# tracy.net
KiCad netlist of a schematic drawn in EAGLE
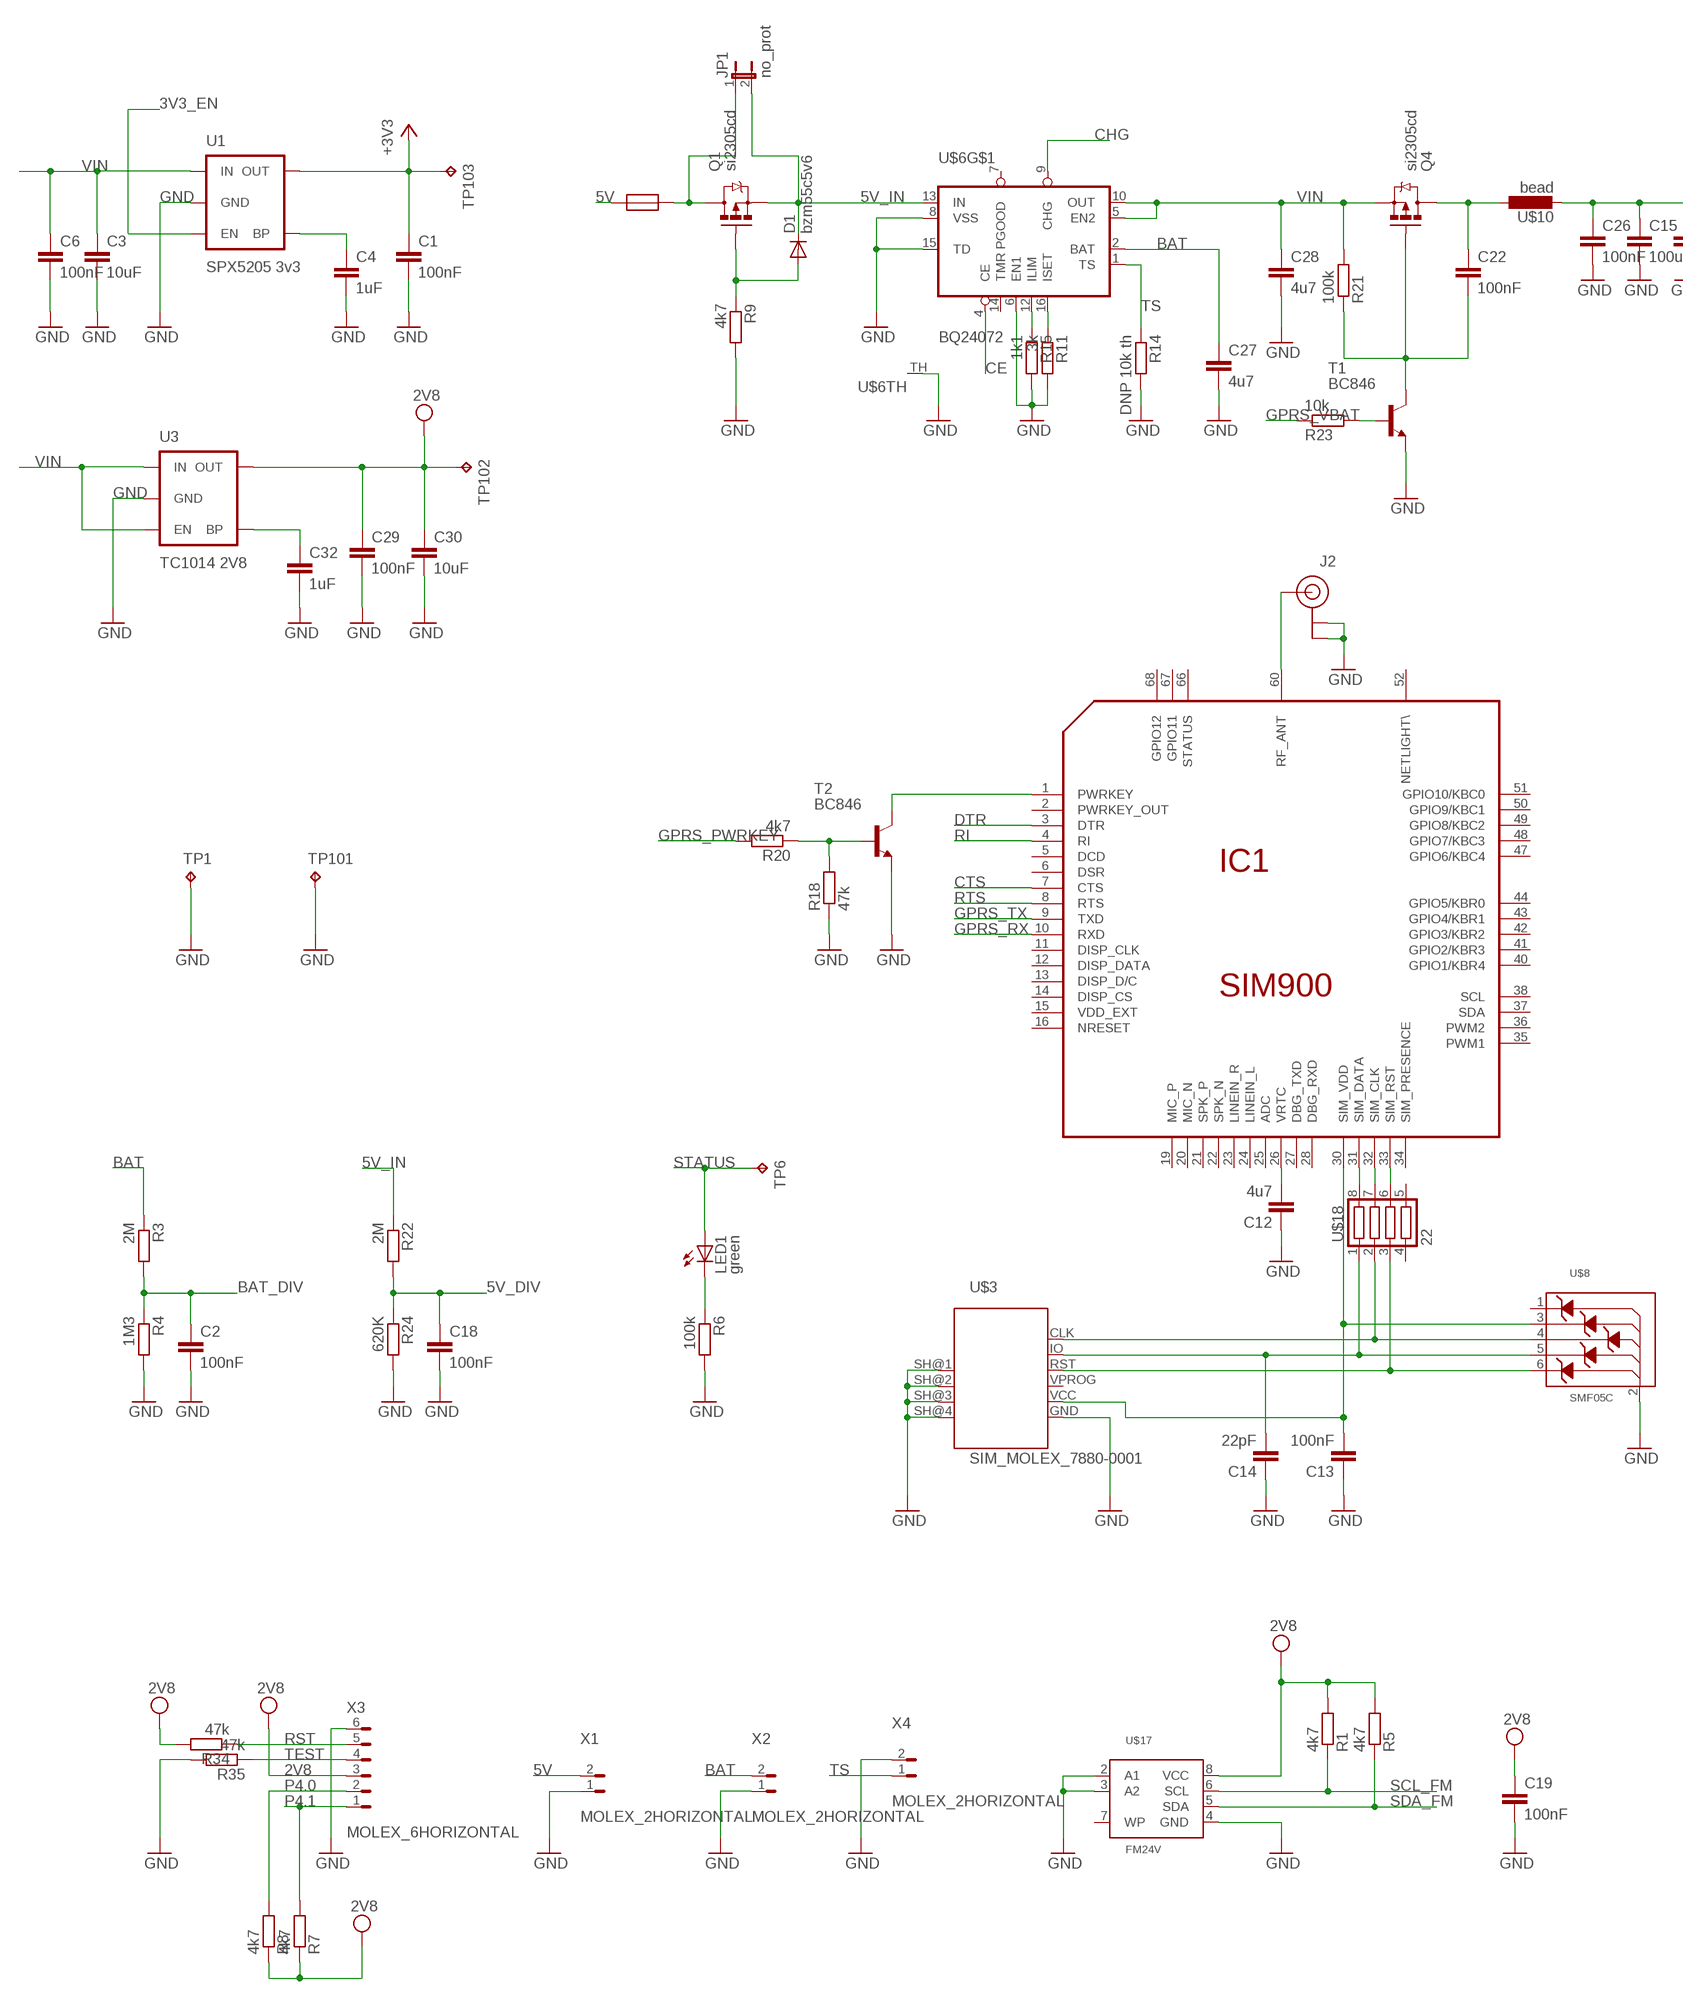
[diagram p0: schematic, sheet 1, part 1 of 2]
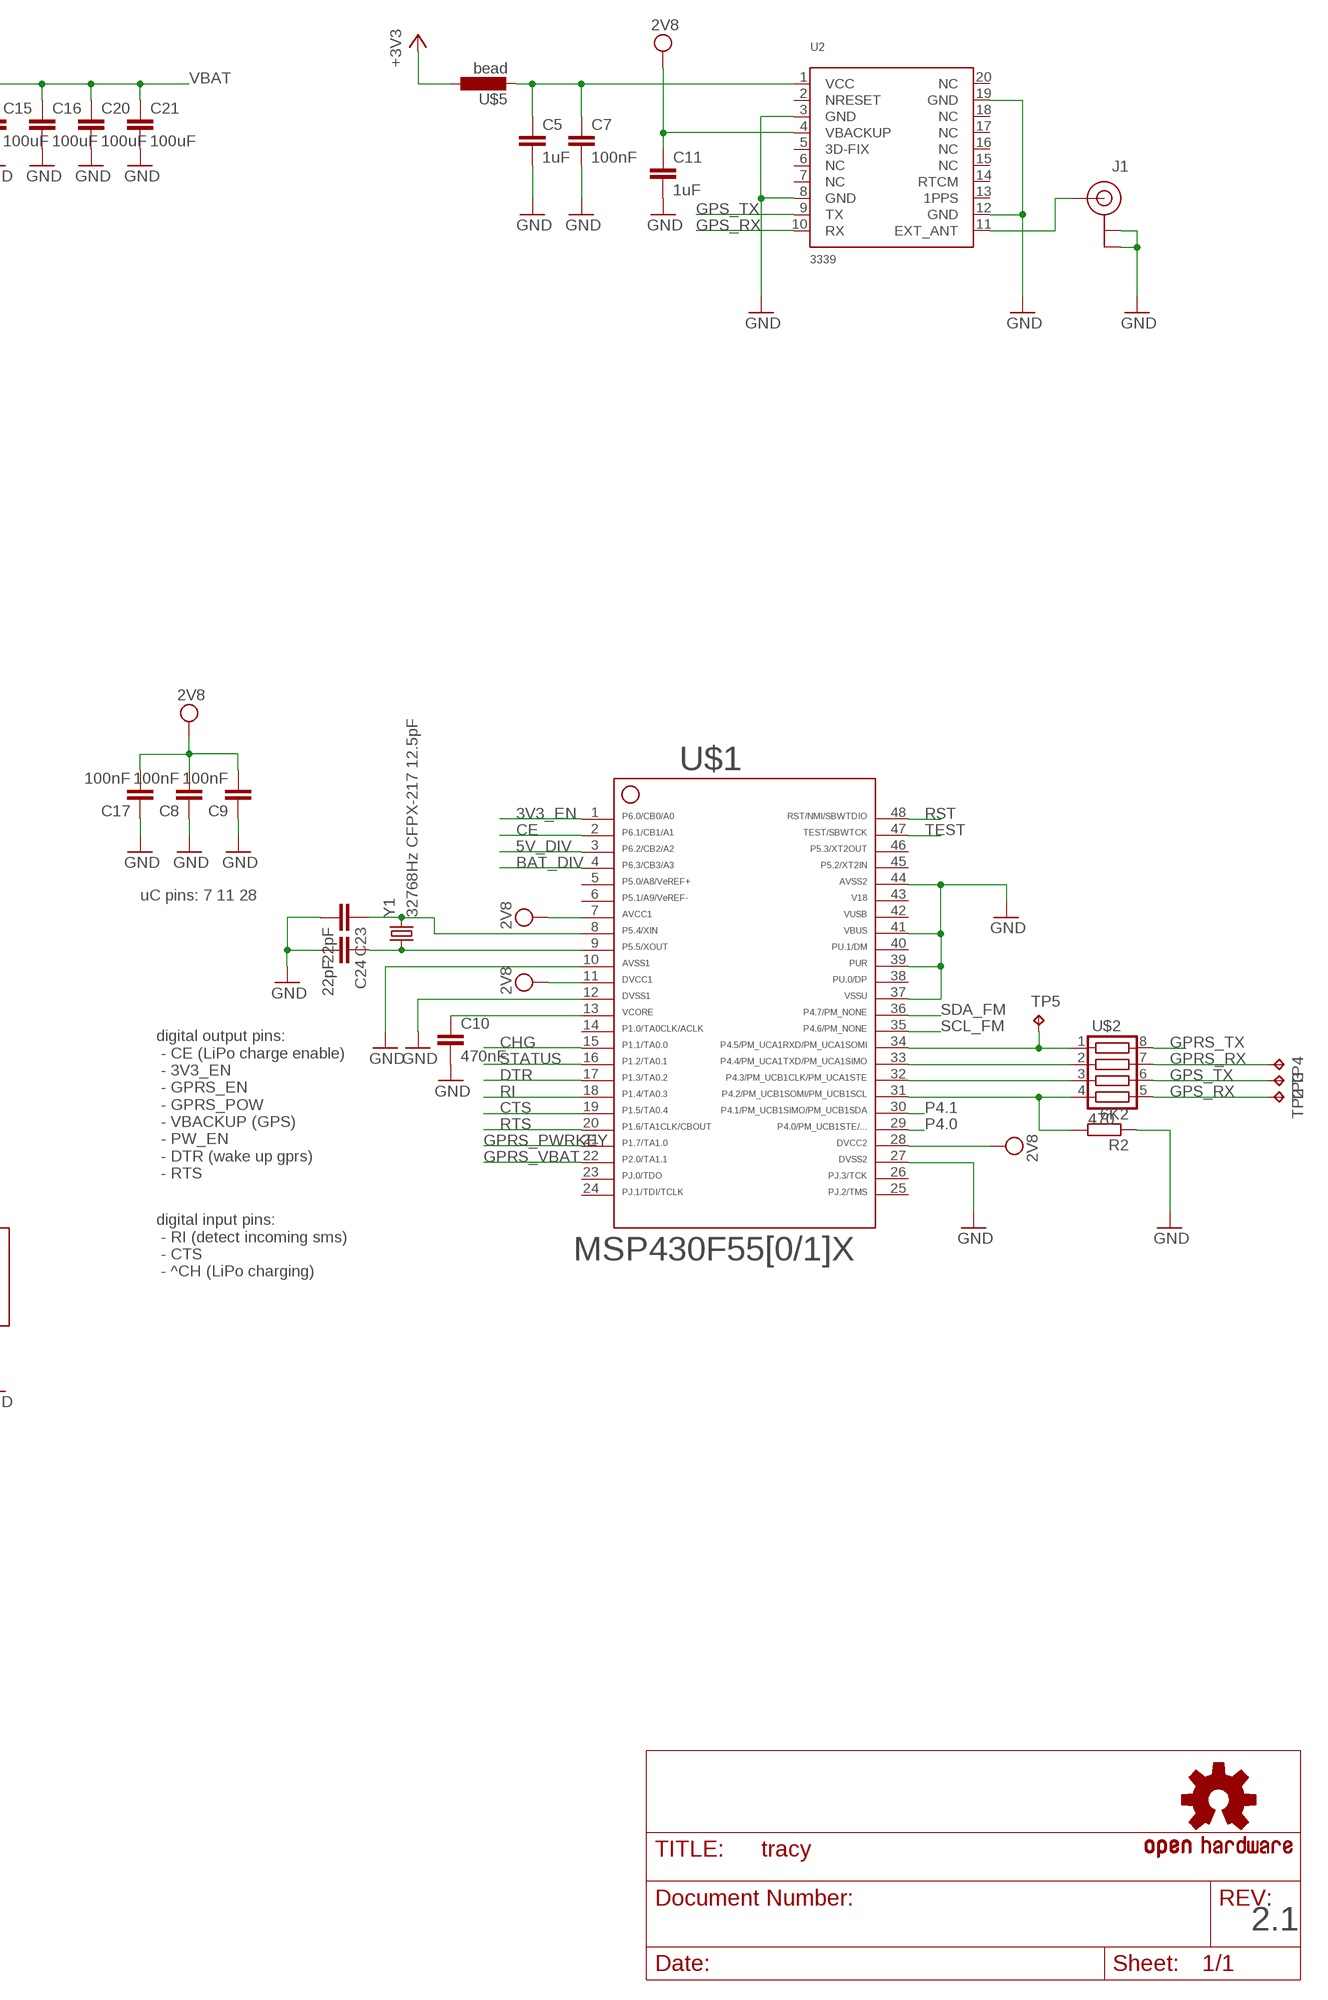
[diagram p1: schematic, sheet 1, part 2 of 2]

(export (version "E")
  (design (tool "Eeschema 10.0.6"))
  (components
    (comp (ref "C1")
      (value "100nF")
      (footprint "eagle-import:C0805")
      (libsource (lib "eagle-import") (part "C-EUC0805"))
    )
    (comp (ref "C2")
      (value "100nF")
      (footprint "eagle-import:C0805")
      (libsource (lib "eagle-import") (part "C-EUC0805"))
    )
    (comp (ref "C3")
      (value "10uF")
      (footprint "eagle-import:C0805")
      (libsource (lib "eagle-import") (part "C-EUC0805"))
    )
    (comp (ref "C4")
      (value "1uF")
      (footprint "eagle-import:C0805")
      (libsource (lib "eagle-import") (part "C-EUC0805"))
    )
    (comp (ref "C5")
      (value "1uF")
      (footprint "eagle-import:C0805")
      (libsource (lib "eagle-import") (part "C-EUC0805"))
    )
    (comp (ref "C6")
      (value "100nF")
      (footprint "eagle-import:C0805")
      (libsource (lib "eagle-import") (part "C-EUC0805"))
    )
    (comp (ref "C7")
      (value "100nF")
      (footprint "eagle-import:C0805")
      (libsource (lib "eagle-import") (part "C-EUC0805"))
    )
    (comp (ref "C8")
      (value "100nF")
      (footprint "eagle-import:C0805")
      (libsource (lib "eagle-import") (part "C-EUC0805"))
    )
    (comp (ref "C9")
      (value "100nF")
      (footprint "eagle-import:C0805")
      (libsource (lib "eagle-import") (part "C-EUC0805"))
    )
    (comp (ref "C10")
      (value "470nF")
      (footprint "eagle-import:C0805")
      (libsource (lib "eagle-import") (part "C-EUC0805"))
    )
    (comp (ref "C11")
      (value "1uF")
      (footprint "eagle-import:C0805")
      (libsource (lib "eagle-import") (part "C-EUC0805"))
    )
    (comp (ref "C12")
      (value "4u7")
      (footprint "eagle-import:C0805")
      (libsource (lib "eagle-import") (part "C-EUC0805"))
    )
    (comp (ref "C13")
      (value "100nF")
      (footprint "eagle-import:C0805")
      (libsource (lib "eagle-import") (part "C-EUC0805"))
    )
    (comp (ref "C14")
      (value "22pF")
      (footprint "eagle-import:C0805")
      (libsource (lib "eagle-import") (part "C-EUC0805"))
    )
    (comp (ref "C15")
      (value "100uF")
      (footprint "eagle-import:C1206")
      (libsource (lib "eagle-import") (part "C-EUC1206"))
    )
    (comp (ref "C16")
      (value "100uF")
      (footprint "eagle-import:C1206")
      (libsource (lib "eagle-import") (part "C-EUC1206"))
    )
    (comp (ref "C17")
      (value "100nF")
      (footprint "eagle-import:C0805")
      (libsource (lib "eagle-import") (part "C-EUC0805"))
    )
    (comp (ref "C18")
      (value "100nF")
      (footprint "eagle-import:C0805")
      (libsource (lib "eagle-import") (part "C-EUC0805"))
    )
    (comp (ref "C19")
      (value "100nF")
      (footprint "eagle-import:C0805")
      (libsource (lib "eagle-import") (part "C-EUC0805"))
    )
    (comp (ref "C20")
      (value "100uF")
      (footprint "eagle-import:C1206")
      (libsource (lib "eagle-import") (part "C-EUC1206"))
    )
    (comp (ref "C21")
      (value "100uF")
      (footprint "eagle-import:C1206")
      (libsource (lib "eagle-import") (part "C-EUC1206"))
    )
    (comp (ref "C22")
      (value "100nF")
      (footprint "eagle-import:C0805")
      (libsource (lib "eagle-import") (part "C-EUC0805"))
    )
    (comp (ref "C23")
      (value "22pF")
      (footprint "eagle-import:C0805")
      (libsource (lib "eagle-import") (part "C-EUC0805"))
    )
    (comp (ref "C24")
      (value "22pF")
      (footprint "eagle-import:C0805")
      (libsource (lib "eagle-import") (part "C-EUC0805"))
    )
    (comp (ref "C26")
      (value "100nF")
      (footprint "eagle-import:C0805")
      (libsource (lib "eagle-import") (part "C-EUC0805"))
    )
    (comp (ref "C27")
      (value "4u7")
      (footprint "eagle-import:C1206")
      (libsource (lib "eagle-import") (part "C-EUC1206"))
    )
    (comp (ref "C28")
      (value "4u7")
      (footprint "eagle-import:C1206")
      (libsource (lib "eagle-import") (part "C-EUC1206"))
    )
    (comp (ref "C29")
      (value "100nF")
      (footprint "eagle-import:C0805")
      (libsource (lib "eagle-import") (part "C-EUC0805"))
    )
    (comp (ref "C30")
      (value "10uF")
      (footprint "eagle-import:C1206")
      (libsource (lib "eagle-import") (part "C-EUC1206"))
    )
    (comp (ref "C32")
      (value "1uF")
      (footprint "eagle-import:C0805")
      (libsource (lib "eagle-import") (part "C-EUC0805"))
    )
    (comp (ref "D1")
      (value "bzm55c5v6")
      (footprint "eagle-import:MICROMELF-W")
      (libsource (lib "eagle-import") (part "DIODE-MICROMELF-W"))
    )
    (comp (ref "IC1")
      (value "SIM900")
      (footprint "eagle-import:SIM900")
      (libsource (lib "eagle-import") (part "SIM900"))
    )
    (comp (ref "J1")
      (value "U.FL")
      (footprint "eagle-import:U.FL")
      (libsource (lib "eagle-import") (part "U.FL"))
    )
    (comp (ref "J2")
      (value "U.FL")
      (footprint "eagle-import:U.FL")
      (libsource (lib "eagle-import") (part "U.FL"))
    )
    (comp (ref "JP1")
      (value "no_prot")
      (footprint "eagle-import:SJ_2S-NO")
      (libsource (lib "eagle-import") (part "JUMPER-2SMD-NO"))
    )
    (comp (ref "LED1")
      (value "green")
      (footprint "eagle-import:CHIPLED_0805")
      (libsource (lib "eagle-import") (part "LEDCHIPLED_0805"))
    )
    (comp (ref "Q1")
      (value "si2305cd")
      (footprint "eagle-import:SOT23-3_POWER")
      (libsource (lib "eagle-import") (part "MOSFET-PCHANNELSMD_POWER"))
    )
    (comp (ref "Q4")
      (value "si2305cd")
      (footprint "eagle-import:SOT23-3_POWER")
      (libsource (lib "eagle-import") (part "MOSFET-PCHANNELSMD_POWER"))
    )
    (comp (ref "R1")
      (value "4k7")
      (footprint "eagle-import:R0805W")
      (libsource (lib "eagle-import") (part "R-EU_R0805W"))
    )
    (comp (ref "R2")
      (value "6K2")
      (footprint "eagle-import:R0805W")
      (libsource (lib "eagle-import") (part "R-EU_R0805W"))
    )
    (comp (ref "R3")
      (value "2M")
      (footprint "eagle-import:R0805W")
      (libsource (lib "eagle-import") (part "R-EU_R0805W"))
    )
    (comp (ref "R4")
      (value "1M3")
      (footprint "eagle-import:R0805W")
      (libsource (lib "eagle-import") (part "R-EU_R0805W"))
    )
    (comp (ref "R5")
      (value "4k7")
      (footprint "eagle-import:R0805W")
      (libsource (lib "eagle-import") (part "R-EU_R0805W"))
    )
    (comp (ref "R6")
      (value "100k")
      (footprint "eagle-import:R0805W")
      (libsource (lib "eagle-import") (part "R-EU_R0805W"))
    )
    (comp (ref "R7")
      (value "4k7")
      (footprint "eagle-import:R0805W")
      (libsource (lib "eagle-import") (part "R-EU_R0805W"))
    )
    (comp (ref "R8")
      (value "4k7")
      (footprint "eagle-import:R0805W")
      (libsource (lib "eagle-import") (part "R-EU_R0805W"))
    )
    (comp (ref "R9")
      (value "4k7")
      (footprint "eagle-import:R0805W")
      (libsource (lib "eagle-import") (part "R-EU_R0805W"))
    )
    (comp (ref "R11")
      (value "3k")
      (footprint "eagle-import:R0805W")
      (libsource (lib "eagle-import") (part "R-EU_R0805W"))
    )
    (comp (ref "R14")
      (value "DNP 10k th")
      (footprint "eagle-import:R0805W")
      (libsource (lib "eagle-import") (part "R-EU_R0805W"))
    )
    (comp (ref "R15")
      (value "1k1")
      (footprint "eagle-import:R0805W")
      (libsource (lib "eagle-import") (part "R-EU_R0805W"))
    )
    (comp (ref "R18")
      (value "47k")
      (footprint "eagle-import:R0805W")
      (libsource (lib "eagle-import") (part "R-EU_R0805W"))
    )
    (comp (ref "R20")
      (value "4k7")
      (footprint "eagle-import:R0805W")
      (libsource (lib "eagle-import") (part "R-EU_R0805W"))
    )
    (comp (ref "R21")
      (value "100k")
      (footprint "eagle-import:R0805W")
      (libsource (lib "eagle-import") (part "R-EU_R0805W"))
    )
    (comp (ref "R22")
      (value "2M")
      (footprint "eagle-import:R0805W")
      (libsource (lib "eagle-import") (part "R-EU_R0805W"))
    )
    (comp (ref "R23")
      (value "10k")
      (footprint "eagle-import:R0805W")
      (libsource (lib "eagle-import") (part "R-EU_R0805W"))
    )
    (comp (ref "R24")
      (value "620K")
      (footprint "eagle-import:R0805W")
      (libsource (lib "eagle-import") (part "R-EU_R0805W"))
    )
    (comp (ref "R34")
      (value "47k")
      (footprint "eagle-import:R0805W")
      (libsource (lib "eagle-import") (part "R-EU_R0805W"))
    )
    (comp (ref "R35")
      (value "47k")
      (footprint "eagle-import:R0805W")
      (libsource (lib "eagle-import") (part "R-EU_R0805W"))
    )
    (comp (ref "T1")
      (value "BC846")
      (footprint "eagle-import:SOT23")
      (libsource (lib "eagle-import") (part "BC846"))
    )
    (comp (ref "T2")
      (value "BC846")
      (footprint "eagle-import:SOT23")
      (libsource (lib "eagle-import") (part "BC846"))
    )
    (comp (ref "TP1")
      (value "TPTP12R")
      (footprint "eagle-import:TP12R")
      (libsource (lib "eagle-import") (part "TPTP12R"))
    )
    (comp (ref "TP2")
      (value "TPTP12R")
      (footprint "eagle-import:TP12R")
      (libsource (lib "eagle-import") (part "TPTP12R"))
    )
    (comp (ref "TP3")
      (value "TPTP12R")
      (footprint "eagle-import:TP12R")
      (libsource (lib "eagle-import") (part "TPTP12R"))
    )
    (comp (ref "TP4")
      (value "TPTP12R")
      (footprint "eagle-import:TP12R")
      (libsource (lib "eagle-import") (part "TPTP12R"))
    )
    (comp (ref "TP5")
      (value "TPTP12R")
      (footprint "eagle-import:TP12R")
      (libsource (lib "eagle-import") (part "TPTP12R"))
    )
    (comp (ref "TP6")
      (value "TPTP12R")
      (footprint "eagle-import:TP12R")
      (libsource (lib "eagle-import") (part "TPTP12R"))
    )
    (comp (ref "TP101")
      (value "TPTP12R")
      (footprint "eagle-import:TP12R")
      (libsource (lib "eagle-import") (part "TPTP12R"))
    )
    (comp (ref "TP102")
      (value "TPTP12R")
      (footprint "eagle-import:TP12R")
      (libsource (lib "eagle-import") (part "TPTP12R"))
    )
    (comp (ref "TP103")
      (value "TPTP12R")
      (footprint "eagle-import:TP12R")
      (libsource (lib "eagle-import") (part "TPTP12R"))
    )
    (comp (ref "U$1")
      (value "MSP430F5510")
      (footprint "eagle-import:PT48")
      (libsource (lib "eagle-import") (part "F55[0/1]X---PT48"))
    )
    (comp (ref "U$2")
      (value "470")
      (footprint "eagle-import:YC164")
      (libsource (lib "eagle-import") (part "RES_ARR"))
    )
    (comp (ref "U$3")
      (value "SIM_MOLEX_7880-0001")
      (footprint "eagle-import:MOLEX_7880-0001")
      (libsource (lib "eagle-import") (part "SIM_MOLEX_7880-0001"))
    )
    (comp (ref "U$5")
      (value "bead")
      (footprint "eagle-import:L0805W")
      (libsource (lib "eagle-import") (part "INDUCTOR"))
    )
    (comp (ref "U$6")
      (value "BQ24072")
      (footprint "eagle-import:S-PVQFN-N16")
      (libsource (lib "eagle-import") (part "BQ24072"))
    )
    (comp (ref "U$7")
      (value "OSHW-LOGOM")
      (footprint "eagle-import:OSHW-LOGO-M")
      (libsource (lib "eagle-import") (part "OSHW-LOGOM"))
    )
    (comp (ref "U$8")
      (value "SMF05C")
      (footprint "eagle-import:SC-88")
      (libsource (lib "eagle-import") (part "SMF05C"))
    )
    (comp (ref "U$9")
      (value "RESETTABLE_0805")
      (footprint "eagle-import:0805W")
      (libsource (lib "eagle-import") (part "RESETTABLE_0805"))
    )
    (comp (ref "U$10")
      (value "bead")
      (footprint "eagle-import:L0805W")
      (libsource (lib "eagle-import") (part "INDUCTOR"))
    )
    (comp (ref "U$17")
      (value "FM24V")
      (footprint "eagle-import:SO-08")
      (libsource (lib "eagle-import") (part "FM24V"))
    )
    (comp (ref "U$18")
      (value "22")
      (footprint "eagle-import:YC164")
      (libsource (lib "eagle-import") (part "RES_ARR"))
    )
    (comp (ref "U1")
      (value "SPX5205 3v3")
      (footprint "eagle-import:SOT23-5")
      (libsource (lib "eagle-import") (part "V_REG_LDOSMD"))
    )
    (comp (ref "U2")
      (value "3339")
      (footprint "eagle-import:FGPMMOPA6H")
      (libsource (lib "eagle-import") (part "GPS_FGPMMOPA6H"))
    )
    (comp (ref "U3")
      (value "TC1014 2V8")
      (footprint "eagle-import:SOT23-5")
      (libsource (lib "eagle-import") (part "V_REG_LDOSMD"))
    )
    (comp (ref "X1")
      (value "MOLEX_2HORIZONTAL")
      (footprint "eagle-import:0530480210")
      (libsource (lib "eagle-import") (part "MOLEX_2HORIZONTAL"))
    )
    (comp (ref "X2")
      (value "MOLEX_2HORIZONTAL")
      (footprint "eagle-import:0530480210")
      (libsource (lib "eagle-import") (part "MOLEX_2HORIZONTAL"))
    )
    (comp (ref "X3")
      (value "MOLEX_6HORIZONTAL")
      (footprint "eagle-import:0530480610")
      (libsource (lib "eagle-import") (part "MOLEX_6HORIZONTAL"))
    )
    (comp (ref "X4")
      (value "MOLEX_2HORIZONTAL")
      (footprint "eagle-import:0530480210")
      (libsource (lib "eagle-import") (part "MOLEX_2HORIZONTAL"))
    )
    (comp (ref "Y1")
      (value "32768Hz CFPX-217 12.5pF")
      (footprint "eagle-import:CRYSTAL-SMD-3.2X1.5")
      (libsource (lib "eagle-import") (part "CRYSTAL3.2X1.5"))
    )
  )
  (nets
    (net (code "1") (name "+3V3") (class "Default")
      (node (ref "C1") (pin "1") (pinfunction "1_1") (pintype "passive"))
      (node (ref "TP103") (pin "TP") (pinfunction "TP_TP") (pintype "input"))
      (node (ref "U$5") (pin "1") (pinfunction "1_1") (pintype "passive"))
      (node (ref "U1") (pin "5") (pinfunction "OUT_5") (pintype "passive"))
    )
    (net (code "2") (name "/3V3_EN") (class "Default")
      (node (ref "U$1") (pin "1") (pinfunction "1_1") (pintype "bidirectional"))
      (node (ref "U1") (pin "3") (pinfunction "EN_3") (pintype "input"))
    )
    (net (code "3") (name "/5V") (class "Default")
      (node (ref "U$9") (pin "1") (pinfunction "P$1_1") (pintype "bidirectional"))
      (node (ref "X1") (pin "2") (pinfunction "1_2") (pintype "passive"))
    )
    (net (code "4") (name "/5V_DIV") (class "Default")
      (node (ref "C18") (pin "1") (pinfunction "1_1") (pintype "passive"))
      (node (ref "R22") (pin "2") (pinfunction "2_2") (pintype "passive"))
      (node (ref "R24") (pin "1") (pinfunction "1_1") (pintype "passive"))
      (node (ref "U$1") (pin "3") (pinfunction "3_3") (pintype "bidirectional"))
    )
    (net (code "5") (name "/5V_IN") (class "Default")
      (node (ref "D1") (pin "C") (pinfunction "C_C") (pintype "passive"))
      (node (ref "JP1") (pin "2") (pinfunction "2_2") (pintype "passive"))
      (node (ref "Q1") (pin "2") (pinfunction "S_2") (pintype "passive"))
      (node (ref "R22") (pin "1") (pinfunction "1_1") (pintype "passive"))
      (node (ref "U$6") (pin "13") (pinfunction "IN_13") (pintype "input"))
    )
    (net (code "6") (name "/42") (class "Default")
      (node (ref "U$1") (pin "42") (pinfunction "42_42") (pintype "power_in"))
    )
    (net (code "7") (name "/43") (class "Default")
      (node (ref "U$1") (pin "43") (pinfunction "43_43") (pintype "power_in"))
    )
    (net (code "8") (name "/46") (class "Default")
      (node (ref "U$1") (pin "46") (pinfunction "46_46") (pintype "power_in"))
    )
    (net (code "9") (name "/BAT") (class "Default")
      (node (ref "C27") (pin "1") (pinfunction "1_1") (pintype "passive"))
      (node (ref "R3") (pin "1") (pinfunction "1_1") (pintype "passive"))
      (node (ref "U$6") (pin "2") (pinfunction "BAT_2") (pintype "input"))
      (node (ref "X2") (pin "2") (pinfunction "1_2") (pintype "passive"))
    )
    (net (code "10") (name "/BAT_DIV") (class "Default")
      (node (ref "C2") (pin "1") (pinfunction "1_1") (pintype "passive"))
      (node (ref "R3") (pin "2") (pinfunction "2_2") (pintype "passive"))
      (node (ref "R4") (pin "1") (pinfunction "1_1") (pintype "passive"))
      (node (ref "U$1") (pin "4") (pinfunction "4_4") (pintype "bidirectional"))
    )
    (net (code "11") (name "/CE") (class "Default")
      (node (ref "U$1") (pin "2") (pinfunction "2_2") (pintype "bidirectional"))
      (node (ref "U$6") (pin "4") (pinfunction "CE_4") (pintype "bidirectional"))
    )
    (net (code "12") (name "/CHG") (class "Default")
      (node (ref "U$1") (pin "15") (pinfunction "15_15") (pintype "bidirectional"))
      (node (ref "U$6") (pin "9") (pinfunction "CHG_9") (pintype "bidirectional"))
    )
    (net (code "13") (name "/CTS") (class "Default")
      (node (ref "IC1") (pin "7") (pinfunction "CTS_7") (pintype "bidirectional"))
      (node (ref "U$1") (pin "19") (pinfunction "19_19") (pintype "bidirectional"))
    )
    (net (code "14") (name "/DTR") (class "Default")
      (node (ref "IC1") (pin "3") (pinfunction "DTR_3") (pintype "bidirectional"))
      (node (ref "U$1") (pin "17") (pinfunction "17_17") (pintype "bidirectional"))
    )
    (net (code "15") (name "/GPRS_PWRKEY") (class "Default")
      (node (ref "R20") (pin "2") (pinfunction "2_2") (pintype "passive"))
      (node (ref "U$1") (pin "21") (pinfunction "21_21") (pintype "bidirectional"))
    )
    (net (code "16") (name "/GPRS_RX") (class "Default")
      (node (ref "IC1") (pin "10") (pinfunction "RXD_10") (pintype "bidirectional"))
      (node (ref "TP4") (pin "TP") (pinfunction "TP_TP") (pintype "input"))
      (node (ref "U$2") (pin "7") (pinfunction "7_7") (pintype "passive"))
    )
    (net (code "17") (name "/GPRS_TX") (class "Default")
      (node (ref "IC1") (pin "9") (pinfunction "TXD_9") (pintype "bidirectional"))
      (node (ref "U$2") (pin "8") (pinfunction "8_8") (pintype "passive"))
    )
    (net (code "18") (name "/GPRS_VBAT") (class "Default")
      (node (ref "R23") (pin "1") (pinfunction "1_1") (pintype "passive"))
      (node (ref "U$1") (pin "22") (pinfunction "22_22") (pintype "bidirectional"))
    )
    (net (code "19") (name "/GPS_RX") (class "Default")
      (node (ref "TP2") (pin "TP") (pinfunction "TP_TP") (pintype "input"))
      (node (ref "U$2") (pin "5") (pinfunction "5_5") (pintype "passive"))
      (node (ref "U2") (pin "10") (pinfunction "RX_10") (pintype "bidirectional"))
    )
    (net (code "20") (name "/GPS_TX") (class "Default")
      (node (ref "TP3") (pin "TP") (pinfunction "TP_TP") (pintype "input"))
      (node (ref "U$2") (pin "6") (pinfunction "6_6") (pintype "passive"))
      (node (ref "U2") (pin "9") (pinfunction "TX_9") (pintype "bidirectional"))
    )
    (net (code "21") (name "/P4.0") (class "Default")
      (node (ref "R8") (pin "2") (pinfunction "2_2") (pintype "passive"))
      (node (ref "U$1") (pin "29") (pinfunction "29_29") (pintype "bidirectional"))
      (node (ref "X3") (pin "2") (pinfunction "5_2") (pintype "passive"))
    )
    (net (code "22") (name "/P4.1") (class "Default")
      (node (ref "R7") (pin "2") (pinfunction "2_2") (pintype "passive"))
      (node (ref "U$1") (pin "30") (pinfunction "30_30") (pintype "bidirectional"))
      (node (ref "X3") (pin "1") (pinfunction "6_1") (pintype "passive"))
    )
    (net (code "23") (name "/RI") (class "Default")
      (node (ref "IC1") (pin "4") (pinfunction "RI_4") (pintype "bidirectional"))
      (node (ref "U$1") (pin "18") (pinfunction "18_18") (pintype "bidirectional"))
    )
    (net (code "24") (name "/RST") (class "Default")
      (node (ref "R34") (pin "1") (pinfunction "1_1") (pintype "passive"))
      (node (ref "U$1") (pin "48") (pinfunction "48_48") (pintype "bidirectional"))
      (node (ref "X3") (pin "5") (pinfunction "2_5") (pintype "passive"))
    )
    (net (code "25") (name "/RTS") (class "Default")
      (node (ref "IC1") (pin "8") (pinfunction "RTS_8") (pintype "bidirectional"))
      (node (ref "U$1") (pin "20") (pinfunction "20_20") (pintype "bidirectional"))
    )
    (net (code "26") (name "/SCL_FM") (class "Default")
      (node (ref "R1") (pin "1") (pinfunction "1_1") (pintype "passive"))
      (node (ref "U$1") (pin "35") (pinfunction "35_35") (pintype "bidirectional"))
      (node (ref "U$17") (pin "6") (pinfunction "SCL_6") (pintype "bidirectional"))
    )
    (net (code "27") (name "/SDA_FM") (class "Default")
      (node (ref "R5") (pin "1") (pinfunction "1_1") (pintype "passive"))
      (node (ref "U$1") (pin "36") (pinfunction "36_36") (pintype "bidirectional"))
      (node (ref "U$17") (pin "5") (pinfunction "SDA_5") (pintype "bidirectional"))
    )
    (net (code "28") (name "/STATUS") (class "Default")
      (node (ref "LED1") (pin "A") (pinfunction "A_A") (pintype "passive"))
      (node (ref "TP6") (pin "TP") (pinfunction "TP_TP") (pintype "input"))
      (node (ref "U$1") (pin "16") (pinfunction "16_16") (pintype "bidirectional"))
    )
    (net (code "29") (name "/TEST") (class "Default")
      (node (ref "R35") (pin "1") (pinfunction "1_1") (pintype "passive"))
      (node (ref "U$1") (pin "47") (pinfunction "47_47") (pintype "input"))
      (node (ref "X3") (pin "4") (pinfunction "3_4") (pintype "passive"))
    )
    (net (code "30") (name "/TS") (class "Default")
      (node (ref "R14") (pin "1") (pinfunction "1_1") (pintype "passive"))
      (node (ref "U$6") (pin "1") (pinfunction "TS_1") (pintype "input"))
      (node (ref "X4") (pin "1") (pinfunction "2_1") (pintype "passive"))
    )
    (net (code "31") (name "/VBAT") (class "Default")
      (node (ref "C15") (pin "1") (pinfunction "1_1") (pintype "passive"))
      (node (ref "C16") (pin "1") (pinfunction "1_1") (pintype "passive"))
      (node (ref "C20") (pin "1") (pinfunction "1_1") (pintype "passive"))
      (node (ref "C21") (pin "1") (pinfunction "1_1") (pintype "passive"))
      (node (ref "C26") (pin "1") (pinfunction "1_1") (pintype "passive"))
      (node (ref "U$10") (pin "2") (pinfunction "2_2") (pintype "passive"))
    )
    (net (code "32") (name "/VIN") (class "Default")
      (node (ref "C28") (pin "1") (pinfunction "1_1") (pintype "passive"))
      (node (ref "C3") (pin "1") (pinfunction "1_1") (pintype "passive"))
      (node (ref "C6") (pin "1") (pinfunction "1_1") (pintype "passive"))
      (node (ref "Q4") (pin "2") (pinfunction "S_2") (pintype "passive"))
      (node (ref "R21") (pin "2") (pinfunction "2_2") (pintype "passive"))
      (node (ref "U$6") (pin "10") (pinfunction "OUT_10") (pintype "output"))
      (node (ref "U$6") (pin "5") (pinfunction "EN2_5") (pintype "input"))
      (node (ref "U1") (pin "1") (pinfunction "IN_1") (pintype "input"))
      (node (ref "U3") (pin "1") (pinfunction "IN_1") (pintype "input"))
      (node (ref "U3") (pin "3") (pinfunction "EN_3") (pintype "input"))
    )
    (net (code "33") (name "2V8") (class "Default")
      (node (ref "C11") (pin "1") (pinfunction "1_1") (pintype "passive"))
      (node (ref "C17") (pin "2") (pinfunction "2_2") (pintype "passive"))
      (node (ref "C19") (pin "1") (pinfunction "1_1") (pintype "passive"))
      (node (ref "C29") (pin "1") (pinfunction "1_1") (pintype "passive"))
      (node (ref "C30") (pin "1") (pinfunction "1_1") (pintype "passive"))
      (node (ref "C8") (pin "2") (pinfunction "2_2") (pintype "passive"))
      (node (ref "C9") (pin "2") (pinfunction "2_2") (pintype "passive"))
      (node (ref "R1") (pin "2") (pinfunction "2_2") (pintype "passive"))
      (node (ref "R34") (pin "2") (pinfunction "2_2") (pintype "passive"))
      (node (ref "R5") (pin "2") (pinfunction "2_2") (pintype "passive"))
      (node (ref "R7") (pin "1") (pinfunction "1_1") (pintype "passive"))
      (node (ref "R8") (pin "1") (pinfunction "1_1") (pintype "passive"))
      (node (ref "TP102") (pin "TP") (pinfunction "TP_TP") (pintype "input"))
      (node (ref "U$1") (pin "11") (pinfunction "11_11") (pintype "power_in"))
      (node (ref "U$1") (pin "28") (pinfunction "28_28") (pintype "power_in"))
      (node (ref "U$1") (pin "7") (pinfunction "7_7") (pintype "power_in"))
      (node (ref "U$17") (pin "8") (pinfunction "VCC_8") (pintype "bidirectional"))
      (node (ref "U2") (pin "4") (pinfunction "VBACKUP_4") (pintype "bidirectional"))
      (node (ref "U3") (pin "5") (pinfunction "OUT_5") (pintype "passive"))
      (node (ref "X3") (pin "3") (pinfunction "4_3") (pintype "passive"))
    )
    (net (code "34") (name "GND") (class "Default")
      (node (ref "C1") (pin "2") (pinfunction "2_2") (pintype "passive"))
      (node (ref "C10") (pin "2") (pinfunction "2_2") (pintype "passive"))
      (node (ref "C11") (pin "2") (pinfunction "2_2") (pintype "passive"))
      (node (ref "C12") (pin "1") (pinfunction "1_1") (pintype "passive"))
      (node (ref "C13") (pin "1") (pinfunction "1_1") (pintype "passive"))
      (node (ref "C14") (pin "1") (pinfunction "1_1") (pintype "passive"))
      (node (ref "C15") (pin "2") (pinfunction "2_2") (pintype "passive"))
      (node (ref "C16") (pin "2") (pinfunction "2_2") (pintype "passive"))
      (node (ref "C17") (pin "1") (pinfunction "1_1") (pintype "passive"))
      (node (ref "C18") (pin "2") (pinfunction "2_2") (pintype "passive"))
      (node (ref "C19") (pin "2") (pinfunction "2_2") (pintype "passive"))
      (node (ref "C2") (pin "2") (pinfunction "2_2") (pintype "passive"))
      (node (ref "C20") (pin "2") (pinfunction "2_2") (pintype "passive"))
      (node (ref "C21") (pin "2") (pinfunction "2_2") (pintype "passive"))
      (node (ref "C23") (pin "2") (pinfunction "2_2") (pintype "passive"))
      (node (ref "C24") (pin "2") (pinfunction "2_2") (pintype "passive"))
      (node (ref "C26") (pin "2") (pinfunction "2_2") (pintype "passive"))
      (node (ref "C27") (pin "2") (pinfunction "2_2") (pintype "passive"))
      (node (ref "C28") (pin "2") (pinfunction "2_2") (pintype "passive"))
      (node (ref "C29") (pin "2") (pinfunction "2_2") (pintype "passive"))
      (node (ref "C3") (pin "2") (pinfunction "2_2") (pintype "passive"))
      (node (ref "C30") (pin "2") (pinfunction "2_2") (pintype "passive"))
      (node (ref "C32") (pin "2") (pinfunction "2_2") (pintype "passive"))
      (node (ref "C4") (pin "2") (pinfunction "2_2") (pintype "passive"))
      (node (ref "C5") (pin "2") (pinfunction "2_2") (pintype "passive"))
      (node (ref "C6") (pin "2") (pinfunction "2_2") (pintype "passive"))
      (node (ref "C7") (pin "2") (pinfunction "2_2") (pintype "passive"))
      (node (ref "C8") (pin "1") (pinfunction "1_1") (pintype "passive"))
      (node (ref "C9") (pin "1") (pinfunction "1_1") (pintype "passive"))
      (node (ref "J1") (pin "P$1") (pinfunction "GND_P$1") (pintype "bidirectional"))
      (node (ref "J1") (pin "P$2") (pinfunction "GND_P$2") (pintype "bidirectional"))
      (node (ref "J2") (pin "P$1") (pinfunction "GND_P$1") (pintype "bidirectional"))
      (node (ref "J2") (pin "P$2") (pinfunction "GND_P$2") (pintype "bidirectional"))
      (node (ref "R11") (pin "2") (pinfunction "2_2") (pintype "passive"))
      (node (ref "R14") (pin "2") (pinfunction "2_2") (pintype "passive"))
      (node (ref "R15") (pin "2") (pinfunction "2_2") (pintype "passive"))
      (node (ref "R18") (pin "1") (pinfunction "1_1") (pintype "passive"))
      (node (ref "R2") (pin "1") (pinfunction "1_1") (pintype "passive"))
      (node (ref "R24") (pin "2") (pinfunction "2_2") (pintype "passive"))
      (node (ref "R35") (pin "2") (pinfunction "2_2") (pintype "passive"))
      (node (ref "R4") (pin "2") (pinfunction "2_2") (pintype "passive"))
      (node (ref "R6") (pin "2") (pinfunction "2_2") (pintype "passive"))
      (node (ref "R9") (pin "2") (pinfunction "2_2") (pintype "passive"))
      (node (ref "T1") (pin "2") (pinfunction "E_2") (pintype "passive"))
      (node (ref "T2") (pin "2") (pinfunction "E_2") (pintype "passive"))
      (node (ref "TP1") (pin "TP") (pinfunction "TP_TP") (pintype "input"))
      (node (ref "TP101") (pin "TP") (pinfunction "TP_TP") (pintype "input"))
      (node (ref "U$1") (pin "10") (pinfunction "10_10") (pintype "power_in"))
      (node (ref "U$1") (pin "12") (pinfunction "12_12") (pintype "power_in"))
      (node (ref "U$1") (pin "27") (pinfunction "27_27") (pintype "power_in"))
      (node (ref "U$1") (pin "37") (pinfunction "37_37") (pintype "power_in"))
      (node (ref "U$1") (pin "39") (pinfunction "39_39") (pintype "bidirectional"))
      (node (ref "U$1") (pin "41") (pinfunction "41_41") (pintype "power_in"))
      (node (ref "U$1") (pin "44") (pinfunction "44_44") (pintype "power_in"))
      (node (ref "U$17") (pin "2") (pinfunction "A1_2") (pintype "bidirectional"))
      (node (ref "U$17") (pin "3") (pinfunction "A2_3") (pintype "bidirectional"))
      (node (ref "U$17") (pin "4") (pinfunction "GND_4") (pintype "bidirectional"))
      (node (ref "U$3") (pin "GND") (pinfunction "GND_GND") (pintype "bidirectional"))
      (node (ref "U$3") (pin "SH@1") (pinfunction "SH_SH@1") (pintype "bidirectional"))
      (node (ref "U$3") (pin "SH@2") (pinfunction "SH_SH@2") (pintype "bidirectional"))
      (node (ref "U$3") (pin "SH@3") (pinfunction "SH_SH@3") (pintype "bidirectional"))
      (node (ref "U$3") (pin "SH@4") (pinfunction "SH_SH@4") (pintype "bidirectional"))
      (node (ref "U$6") (pin "15") (pinfunction "TD_15") (pintype "bidirectional"))
      (node (ref "U$6") (pin "6") (pinfunction "EN1_6") (pintype "bidirectional"))
      (node (ref "U$6") (pin "8") (pinfunction "VSS_8") (pintype "power_in"))
      (node (ref "U$6") (pin "TH") (pinfunction "TH_TH") (pintype "passive"))
      (node (ref "U$8") (pin "2") (pinfunction "ANODE_2") (pintype "passive"))
      (node (ref "U1") (pin "2") (pinfunction "GND_2") (pintype "input"))
      (node (ref "U2") (pin "12") (pinfunction "GND_12") (pintype "bidirectional"))
      (node (ref "U2") (pin "19") (pinfunction "GND_19") (pintype "bidirectional"))
      (node (ref "U2") (pin "3") (pinfunction "GND_3") (pintype "bidirectional"))
      (node (ref "U2") (pin "8") (pinfunction "GND_8") (pintype "bidirectional"))
      (node (ref "U3") (pin "2") (pinfunction "GND_2") (pintype "input"))
      (node (ref "X1") (pin "1") (pinfunction "2_1") (pintype "passive"))
      (node (ref "X2") (pin "1") (pinfunction "2_1") (pintype "passive"))
      (node (ref "X3") (pin "6") (pinfunction "1_6") (pintype "passive"))
      (node (ref "X4") (pin "2") (pinfunction "1_2") (pintype "passive"))
    )
    (net (code "35") (name "Net-(C10-Pad1)") (class "Default")
      (node (ref "C10") (pin "1") (pinfunction "1_1") (pintype "passive"))
      (node (ref "U$1") (pin "13") (pinfunction "13_13") (pintype "power_in"))
    )
    (net (code "36") (name "Net-(IC1A-PWRKEY)") (class "Default")
      (node (ref "IC1") (pin "1") (pinfunction "PWRKEY_1") (pintype "bidirectional"))
      (node (ref "T2") (pin "3") (pinfunction "C_3") (pintype "passive"))
    )
    (net (code "37") (name "Net-(IC1A-RF_ANT)") (class "Default")
      (node (ref "IC1") (pin "60") (pinfunction "RF_ANT_60") (pintype "bidirectional"))
      (node (ref "J2") (pin "P$3") (pinfunction "SIGNAL_P$3") (pintype "bidirectional"))
    )
    (net (code "38") (name "Net-(IC1A-SIM_CLK)") (class "Default")
      (node (ref "IC1") (pin "32") (pinfunction "SIM_CLK_32") (pintype "bidirectional"))
      (node (ref "U$18") (pin "7") (pinfunction "7_7") (pintype "passive"))
    )
    (net (code "39") (name "Net-(IC1A-SIM_DATA)") (class "Default")
      (node (ref "IC1") (pin "31") (pinfunction "SIM_DATA_31") (pintype "bidirectional"))
      (node (ref "U$18") (pin "8") (pinfunction "8_8") (pintype "passive"))
    )
    (net (code "40") (name "Net-(IC1A-SIM_RST)") (class "Default")
      (node (ref "IC1") (pin "33") (pinfunction "SIM_RST_33") (pintype "bidirectional"))
      (node (ref "U$18") (pin "6") (pinfunction "6_6") (pintype "passive"))
    )
    (net (code "41") (name "Net-(IC1A-SIM_VDD)") (class "Default")
      (node (ref "C13") (pin "2") (pinfunction "2_2") (pintype "passive"))
      (node (ref "IC1") (pin "30") (pinfunction "SIM_VDD_30") (pintype "bidirectional"))
      (node (ref "U$3") (pin "VCC") (pinfunction "VCC_VCC") (pintype "bidirectional"))
      (node (ref "U$8") (pin "3") (pinfunction "CATODE2_3") (pintype "passive"))
    )
    (net (code "42") (name "Net-(IC1A-VRTC)") (class "Default")
      (node (ref "C12") (pin "2") (pinfunction "2_2") (pintype "passive"))
      (node (ref "IC1") (pin "26") (pinfunction "VRTC_26") (pintype "bidirectional"))
    )
    (net (code "43") (name "Net-(J1-SIGNAL)") (class "Default")
      (node (ref "J1") (pin "P$3") (pinfunction "SIGNAL_P$3") (pintype "bidirectional"))
      (node (ref "U2") (pin "11") (pinfunction "EXT_ANT_11") (pintype "bidirectional"))
    )
    (net (code "44") (name "Net-(LED1-PadC)") (class "Default")
      (node (ref "LED1") (pin "C") (pinfunction "C_C") (pintype "passive"))
      (node (ref "R6") (pin "1") (pinfunction "1_1") (pintype "passive"))
    )
    (net (code "45") (name "Net-(Q1-D)") (class "Default")
      (node (ref "JP1") (pin "1") (pinfunction "1_1") (pintype "passive"))
      (node (ref "Q1") (pin "3") (pinfunction "D_3") (pintype "passive"))
      (node (ref "U$9") (pin "2") (pinfunction "P$2_2") (pintype "bidirectional"))
    )
    (net (code "46") (name "Net-(Q1-G)") (class "Default")
      (node (ref "D1") (pin "A") (pinfunction "A_A") (pintype "passive"))
      (node (ref "Q1") (pin "1") (pinfunction "G_1") (pintype "passive"))
      (node (ref "R9") (pin "1") (pinfunction "1_1") (pintype "passive"))
    )
    (net (code "47") (name "Net-(Q4-D)") (class "Default")
      (node (ref "C22") (pin "1") (pinfunction "1_1") (pintype "passive"))
      (node (ref "Q4") (pin "3") (pinfunction "D_3") (pintype "passive"))
      (node (ref "U$10") (pin "1") (pinfunction "1_1") (pintype "passive"))
    )
    (net (code "48") (name "Net-(Q4-G)") (class "Default")
      (node (ref "C22") (pin "2") (pinfunction "2_2") (pintype "passive"))
      (node (ref "Q4") (pin "1") (pinfunction "G_1") (pintype "passive"))
      (node (ref "R21") (pin "1") (pinfunction "1_1") (pintype "passive"))
      (node (ref "T1") (pin "3") (pinfunction "C_3") (pintype "passive"))
    )
    (net (code "49") (name "Net-(R2-Pad2)") (class "Default")
      (node (ref "R2") (pin "2") (pinfunction "2_2") (pintype "passive"))
      (node (ref "U$1") (pin "31") (pinfunction "31_31") (pintype "bidirectional"))
      (node (ref "U$2") (pin "4") (pinfunction "4_4") (pintype "passive"))
    )
    (net (code "50") (name "Net-(T1-B)") (class "Default")
      (node (ref "R23") (pin "2") (pinfunction "2_2") (pintype "passive"))
      (node (ref "T1") (pin "1") (pinfunction "B_1") (pintype "passive"))
    )
    (net (code "51") (name "Net-(T2-B)") (class "Default")
      (node (ref "R18") (pin "2") (pinfunction "2_2") (pintype "passive"))
      (node (ref "R20") (pin "1") (pinfunction "1_1") (pintype "passive"))
      (node (ref "T2") (pin "1") (pinfunction "B_1") (pintype "passive"))
    )
    (net (code "52") (name "Net-(TP5-PadTP)") (class "Default")
      (node (ref "TP5") (pin "TP") (pinfunction "TP_TP") (pintype "input"))
      (node (ref "U$1") (pin "34") (pinfunction "34_34") (pintype "bidirectional"))
      (node (ref "U$2") (pin "1") (pinfunction "1_1") (pintype "passive"))
    )
    (net (code "53") (name "Net-(U$1-Pad32)") (class "Default")
      (node (ref "U$1") (pin "32") (pinfunction "32_32") (pintype "bidirectional"))
      (node (ref "U$2") (pin "3") (pinfunction "3_3") (pintype "passive"))
    )
    (net (code "54") (name "Net-(U$1-Pad33)") (class "Default")
      (node (ref "U$1") (pin "33") (pinfunction "33_33") (pintype "bidirectional"))
      (node (ref "U$2") (pin "2") (pinfunction "2_2") (pintype "passive"))
    )
    (net (code "55") (name "Net-(U$6A-ILIM)") (class "Default")
      (node (ref "R15") (pin "1") (pinfunction "1_1") (pintype "passive"))
      (node (ref "U$6") (pin "12") (pinfunction "ILIM_12") (pintype "bidirectional"))
    )
    (net (code "56") (name "Net-(U$6A-ISET)") (class "Default")
      (node (ref "R11") (pin "1") (pinfunction "1_1") (pintype "passive"))
      (node (ref "U$6") (pin "16") (pinfunction "ISET_16") (pintype "input"))
    )
    (net (code "57") (name "Net-(U$8-CATODE3)") (class "Default")
      (node (ref "U$18") (pin "2") (pinfunction "2_2") (pintype "passive"))
      (node (ref "U$3") (pin "CLK") (pinfunction "CLK_CLK") (pintype "bidirectional"))
      (node (ref "U$8") (pin "4") (pinfunction "CATODE3_4") (pintype "passive"))
    )
    (net (code "58") (name "Net-(U$8-CATODE4)") (class "Default")
      (node (ref "C14") (pin "2") (pinfunction "2_2") (pintype "passive"))
      (node (ref "U$18") (pin "1") (pinfunction "1_1") (pintype "passive"))
      (node (ref "U$3") (pin "IO") (pinfunction "IO_IO") (pintype "bidirectional"))
      (node (ref "U$8") (pin "5") (pinfunction "CATODE4_5") (pintype "passive"))
    )
    (net (code "59") (name "Net-(U$8-CATODE5)") (class "Default")
      (node (ref "U$18") (pin "3") (pinfunction "3_3") (pintype "passive"))
      (node (ref "U$3") (pin "RST") (pinfunction "RST_RST") (pintype "bidirectional"))
      (node (ref "U$8") (pin "6") (pinfunction "CATODE5_6") (pintype "passive"))
    )
    (net (code "60") (name "Net-(U1-BP)") (class "Default")
      (node (ref "C4") (pin "1") (pinfunction "1_1") (pintype "passive"))
      (node (ref "U1") (pin "4") (pinfunction "BP_4") (pintype "input"))
    )
    (net (code "61") (name "Net-(U2-VCC)") (class "Default")
      (node (ref "C5") (pin "1") (pinfunction "1_1") (pintype "passive"))
      (node (ref "C7") (pin "1") (pinfunction "1_1") (pintype "passive"))
      (node (ref "U$5") (pin "2") (pinfunction "2_2") (pintype "passive"))
      (node (ref "U2") (pin "1") (pinfunction "VCC_1") (pintype "bidirectional"))
    )
    (net (code "62") (name "Net-(U3-BP)") (class "Default")
      (node (ref "C32") (pin "1") (pinfunction "1_1") (pintype "passive"))
      (node (ref "U3") (pin "4") (pinfunction "BP_4") (pintype "input"))
    )
    (net (code "63") (name "Net-(Y1-1)") (class "Default")
      (node (ref "C24") (pin "1") (pinfunction "1_1") (pintype "passive"))
      (node (ref "U$1") (pin "9") (pinfunction "9_9") (pintype "bidirectional"))
      (node (ref "Y1") (pin "P$1") (pinfunction "1_P$1") (pintype "passive"))
    )
    (net (code "64") (name "Net-(Y1-2)") (class "Default")
      (node (ref "C23") (pin "1") (pinfunction "1_1") (pintype "passive"))
      (node (ref "U$1") (pin "8") (pinfunction "8_8") (pintype "bidirectional"))
      (node (ref "Y1") (pin "P$2") (pinfunction "2_P$2") (pintype "passive"))
    )
    (net (code "65") (name "unconnected-(IC1A-ADC-Pad25)") (class "Default")
      (node (ref "IC1") (pin "25") (pinfunction "ADC_25") (pintype "bidirectional"))
    )
    (net (code "66") (name "unconnected-(IC1A-DBG_RXD-Pad28)") (class "Default")
      (node (ref "IC1") (pin "28") (pinfunction "DBG_RXD_28") (pintype "bidirectional"))
    )
    (net (code "67") (name "unconnected-(IC1A-DBG_TXD-Pad27)") (class "Default")
      (node (ref "IC1") (pin "27") (pinfunction "DBG_TXD_27") (pintype "bidirectional"))
    )
    (net (code "68") (name "unconnected-(IC1A-DCD-Pad5)") (class "Default")
      (node (ref "IC1") (pin "5") (pinfunction "DCD_5") (pintype "bidirectional"))
    )
    (net (code "69") (name "unconnected-(IC1A-DISP_CLK-Pad11)") (class "Default")
      (node (ref "IC1") (pin "11") (pinfunction "DISP_CLK_11") (pintype "bidirectional"))
    )
    (net (code "70") (name "unconnected-(IC1A-DISP_CS-Pad14)") (class "Default")
      (node (ref "IC1") (pin "14") (pinfunction "DISP_CS_14") (pintype "bidirectional"))
    )
    (net (code "71") (name "unconnected-(IC1A-DISP_DATA-Pad12)") (class "Default")
      (node (ref "IC1") (pin "12") (pinfunction "DISP_DATA_12") (pintype "bidirectional"))
    )
    (net (code "72") (name "unconnected-(IC1A-DISP_D{slash}C-Pad13)") (class "Default")
      (node (ref "IC1") (pin "13") (pinfunction "DISP_D/C_13") (pintype "bidirectional"))
    )
    (net (code "73") (name "unconnected-(IC1A-DSR-Pad6)") (class "Default")
      (node (ref "IC1") (pin "6") (pinfunction "DSR_6") (pintype "bidirectional"))
    )
    (net (code "74") (name "unconnected-(IC1A-GPIO1{slash}KBR4-Pad40)") (class "Default")
      (node (ref "IC1") (pin "40") (pinfunction "GPIO1/KBR4_40") (pintype "bidirectional"))
    )
    (net (code "75") (name "unconnected-(IC1A-GPIO2{slash}KBR3-Pad41)") (class "Default")
      (node (ref "IC1") (pin "41") (pinfunction "GPIO2/KBR3_41") (pintype "bidirectional"))
    )
    (net (code "76") (name "unconnected-(IC1A-GPIO3{slash}KBR2-Pad42)") (class "Default")
      (node (ref "IC1") (pin "42") (pinfunction "GPIO3/KBR2_42") (pintype "bidirectional"))
    )
    (net (code "77") (name "unconnected-(IC1A-GPIO4{slash}KBR1-Pad43)") (class "Default")
      (node (ref "IC1") (pin "43") (pinfunction "GPIO4/KBR1_43") (pintype "bidirectional"))
    )
    (net (code "78") (name "unconnected-(IC1A-GPIO5{slash}KBR0-Pad44)") (class "Default")
      (node (ref "IC1") (pin "44") (pinfunction "GPIO5/KBR0_44") (pintype "bidirectional"))
    )
    (net (code "79") (name "unconnected-(IC1A-GPIO6{slash}KBC4-Pad47)") (class "Default")
      (node (ref "IC1") (pin "47") (pinfunction "GPIO6/KBC4_47") (pintype "bidirectional"))
    )
    (net (code "80") (name "unconnected-(IC1A-GPIO7{slash}KBC3-Pad48)") (class "Default")
      (node (ref "IC1") (pin "48") (pinfunction "GPIO7/KBC3_48") (pintype "bidirectional"))
    )
    (net (code "81") (name "unconnected-(IC1A-GPIO8{slash}KBC2-Pad49)") (class "Default")
      (node (ref "IC1") (pin "49") (pinfunction "GPIO8/KBC2_49") (pintype "bidirectional"))
    )
    (net (code "82") (name "unconnected-(IC1A-GPIO9{slash}KBC1-Pad50)") (class "Default")
      (node (ref "IC1") (pin "50") (pinfunction "GPIO9/KBC1_50") (pintype "bidirectional"))
    )
    (net (code "83") (name "unconnected-(IC1A-GPIO10{slash}KBC0-Pad51)") (class "Default")
      (node (ref "IC1") (pin "51") (pinfunction "GPIO10/KBC0_51") (pintype "bidirectional"))
    )
    (net (code "84") (name "unconnected-(IC1A-GPIO11-Pad67)") (class "Default")
      (node (ref "IC1") (pin "67") (pinfunction "GPIO11_67") (pintype "bidirectional"))
    )
    (net (code "85") (name "unconnected-(IC1A-GPIO12-Pad68)") (class "Default")
      (node (ref "IC1") (pin "68") (pinfunction "GPIO12_68") (pintype "bidirectional"))
    )
    (net (code "86") (name "unconnected-(IC1A-LINEIN_L-Pad24)") (class "Default")
      (node (ref "IC1") (pin "24") (pinfunction "LINEIN_L_24") (pintype "bidirectional"))
    )
    (net (code "87") (name "unconnected-(IC1A-LINEIN_R-Pad23)") (class "Default")
      (node (ref "IC1") (pin "23") (pinfunction "LINEIN_R_23") (pintype "bidirectional"))
    )
    (net (code "88") (name "unconnected-(IC1A-MIC_N-Pad20)") (class "Default")
      (node (ref "IC1") (pin "20") (pinfunction "MIC_N_20") (pintype "bidirectional"))
    )
    (net (code "89") (name "unconnected-(IC1A-MIC_P-Pad19)") (class "Default")
      (node (ref "IC1") (pin "19") (pinfunction "MIC_P_19") (pintype "bidirectional"))
    )
    (net (code "90") (name "unconnected-(IC1A-NETLIGHT\\-Pad52)") (class "Default")
      (node (ref "IC1") (pin "52") (pinfunction "NETLIGHT\\_52") (pintype "bidirectional"))
    )
    (net (code "91") (name "unconnected-(IC1A-NRESET-Pad16)") (class "Default")
      (node (ref "IC1") (pin "16") (pinfunction "NRESET_16") (pintype "bidirectional"))
    )
    (net (code "92") (name "unconnected-(IC1A-PWM1-Pad35)") (class "Default")
      (node (ref "IC1") (pin "35") (pinfunction "PWM1_35") (pintype "bidirectional"))
    )
    (net (code "93") (name "unconnected-(IC1A-PWM2-Pad36)") (class "Default")
      (node (ref "IC1") (pin "36") (pinfunction "PWM2_36") (pintype "bidirectional"))
    )
    (net (code "94") (name "unconnected-(IC1A-PWRKEY_OUT-Pad2)") (class "Default")
      (node (ref "IC1") (pin "2") (pinfunction "PWRKEY_OUT_2") (pintype "bidirectional"))
    )
    (net (code "95") (name "unconnected-(IC1A-SCL-Pad38)") (class "Default")
      (node (ref "IC1") (pin "38") (pinfunction "SCL_38") (pintype "bidirectional"))
    )
    (net (code "96") (name "unconnected-(IC1A-SDA-Pad37)") (class "Default")
      (node (ref "IC1") (pin "37") (pinfunction "SDA_37") (pintype "bidirectional"))
    )
    (net (code "97") (name "unconnected-(IC1A-SIM_PRESENCE-Pad34)") (class "Default")
      (node (ref "IC1") (pin "34") (pinfunction "SIM_PRESENCE_34") (pintype "bidirectional"))
    )
    (net (code "98") (name "unconnected-(IC1A-SPK_N-Pad22)") (class "Default")
      (node (ref "IC1") (pin "22") (pinfunction "SPK_N_22") (pintype "bidirectional"))
    )
    (net (code "99") (name "unconnected-(IC1A-SPK_P-Pad21)") (class "Default")
      (node (ref "IC1") (pin "21") (pinfunction "SPK_P_21") (pintype "bidirectional"))
    )
    (net (code "100") (name "unconnected-(IC1A-STATUS-Pad66)") (class "Default")
      (node (ref "IC1") (pin "66") (pinfunction "STATUS_66") (pintype "bidirectional"))
    )
    (net (code "101") (name "unconnected-(IC1A-VDD_EXT-Pad15)") (class "Default")
      (node (ref "IC1") (pin "15") (pinfunction "VDD_EXT_15") (pintype "bidirectional"))
    )
    (net (code "102") (name "unconnected-(U$1-Pad5)") (class "Default")
      (node (ref "U$1") (pin "5") (pinfunction "5_5") (pintype "bidirectional"))
    )
    (net (code "103") (name "unconnected-(U$1-Pad6)") (class "Default")
      (node (ref "U$1") (pin "6") (pinfunction "6_6") (pintype "bidirectional"))
    )
    (net (code "104") (name "unconnected-(U$1-Pad14)") (class "Default")
      (node (ref "U$1") (pin "14") (pinfunction "14_14") (pintype "bidirectional"))
    )
    (net (code "105") (name "unconnected-(U$1-Pad23)") (class "Default")
      (node (ref "U$1") (pin "23") (pinfunction "23_23") (pintype "bidirectional"))
    )
    (net (code "106") (name "unconnected-(U$1-Pad24)") (class "Default")
      (node (ref "U$1") (pin "24") (pinfunction "24_24") (pintype "bidirectional"))
    )
    (net (code "107") (name "unconnected-(U$1-Pad25)") (class "Default")
      (node (ref "U$1") (pin "25") (pinfunction "25_25") (pintype "bidirectional"))
    )
    (net (code "108") (name "unconnected-(U$1-Pad26)") (class "Default")
      (node (ref "U$1") (pin "26") (pinfunction "26_26") (pintype "bidirectional"))
    )
    (net (code "109") (name "unconnected-(U$1-Pad38)") (class "Default")
      (node (ref "U$1") (pin "38") (pinfunction "38_38") (pintype "bidirectional"))
    )
    (net (code "110") (name "unconnected-(U$1-Pad40)") (class "Default")
      (node (ref "U$1") (pin "40") (pinfunction "40_40") (pintype "bidirectional"))
    )
    (net (code "111") (name "unconnected-(U$1-Pad45)") (class "Default")
      (node (ref "U$1") (pin "45") (pinfunction "45_45") (pintype "bidirectional"))
    )
    (net (code "112") (name "unconnected-(U$3-PadVPROG)") (class "Default")
      (node (ref "U$3") (pin "VPROG") (pinfunction "VPROG_VPROG") (pintype "bidirectional"))
    )
    (net (code "113") (name "unconnected-(U$6A-PGOOD-Pad7)") (class "Default")
      (node (ref "U$6") (pin "7") (pinfunction "PGOOD_7") (pintype "bidirectional"))
    )
    (net (code "114") (name "unconnected-(U$6A-TMR-Pad14)") (class "Default")
      (node (ref "U$6") (pin "14") (pinfunction "TMR_14") (pintype "bidirectional"))
    )
    (net (code "115") (name "unconnected-(U$8-CATODE1-Pad1)") (class "Default")
      (node (ref "U$8") (pin "1") (pinfunction "CATODE1_1") (pintype "passive"))
    )
    (net (code "116") (name "unconnected-(U$17-WP-Pad7)") (class "Default")
      (node (ref "U$17") (pin "7") (pinfunction "WP_7") (pintype "bidirectional"))
    )
    (net (code "117") (name "unconnected-(U$18-Pad4)") (class "Default")
      (node (ref "U$18") (pin "4") (pinfunction "4_4") (pintype "passive"))
    )
    (net (code "118") (name "unconnected-(U$18-Pad5)") (class "Default")
      (node (ref "U$18") (pin "5") (pinfunction "5_5") (pintype "passive"))
    )
    (net (code "119") (name "unconnected-(U2-1PPS-Pad13)") (class "Default")
      (node (ref "U2") (pin "13") (pinfunction "1PPS_13") (pintype "bidirectional"))
    )
    (net (code "120") (name "unconnected-(U2-3D-FIX-Pad5)") (class "Default")
      (node (ref "U2") (pin "5") (pinfunction "3D-FIX_5") (pintype "bidirectional"))
    )
    (net (code "121") (name "unconnected-(U2-NC-Pad6)") (class "Default")
      (node (ref "U2") (pin "6") (pinfunction "NC_6") (pintype "bidirectional"))
    )
    (net (code "122") (name "unconnected-(U2-NC-Pad7)") (class "Default")
      (node (ref "U2") (pin "7") (pinfunction "NC_7") (pintype "bidirectional"))
    )
    (net (code "123") (name "unconnected-(U2-NC-Pad15)") (class "Default")
      (node (ref "U2") (pin "15") (pinfunction "NC_15") (pintype "bidirectional"))
    )
    (net (code "124") (name "unconnected-(U2-NC-Pad16)") (class "Default")
      (node (ref "U2") (pin "16") (pinfunction "NC_16") (pintype "bidirectional"))
    )
    (net (code "125") (name "unconnected-(U2-NC-Pad17)") (class "Default")
      (node (ref "U2") (pin "17") (pinfunction "NC_17") (pintype "bidirectional"))
    )
    (net (code "126") (name "unconnected-(U2-NC-Pad18)") (class "Default")
      (node (ref "U2") (pin "18") (pinfunction "NC_18") (pintype "bidirectional"))
    )
    (net (code "127") (name "unconnected-(U2-NC-Pad20)") (class "Default")
      (node (ref "U2") (pin "20") (pinfunction "NC_20") (pintype "bidirectional"))
    )
    (net (code "128") (name "unconnected-(U2-NRESET-Pad2)") (class "Default")
      (node (ref "U2") (pin "2") (pinfunction "NRESET_2") (pintype "bidirectional"))
    )
    (net (code "129") (name "unconnected-(U2-RTCM-Pad14)") (class "Default")
      (node (ref "U2") (pin "14") (pinfunction "RTCM_14") (pintype "bidirectional"))
    )
  )
)
